# TiltMouseSurfaceMount.net
KiCad netlist of a schematic drawn in EAGLE
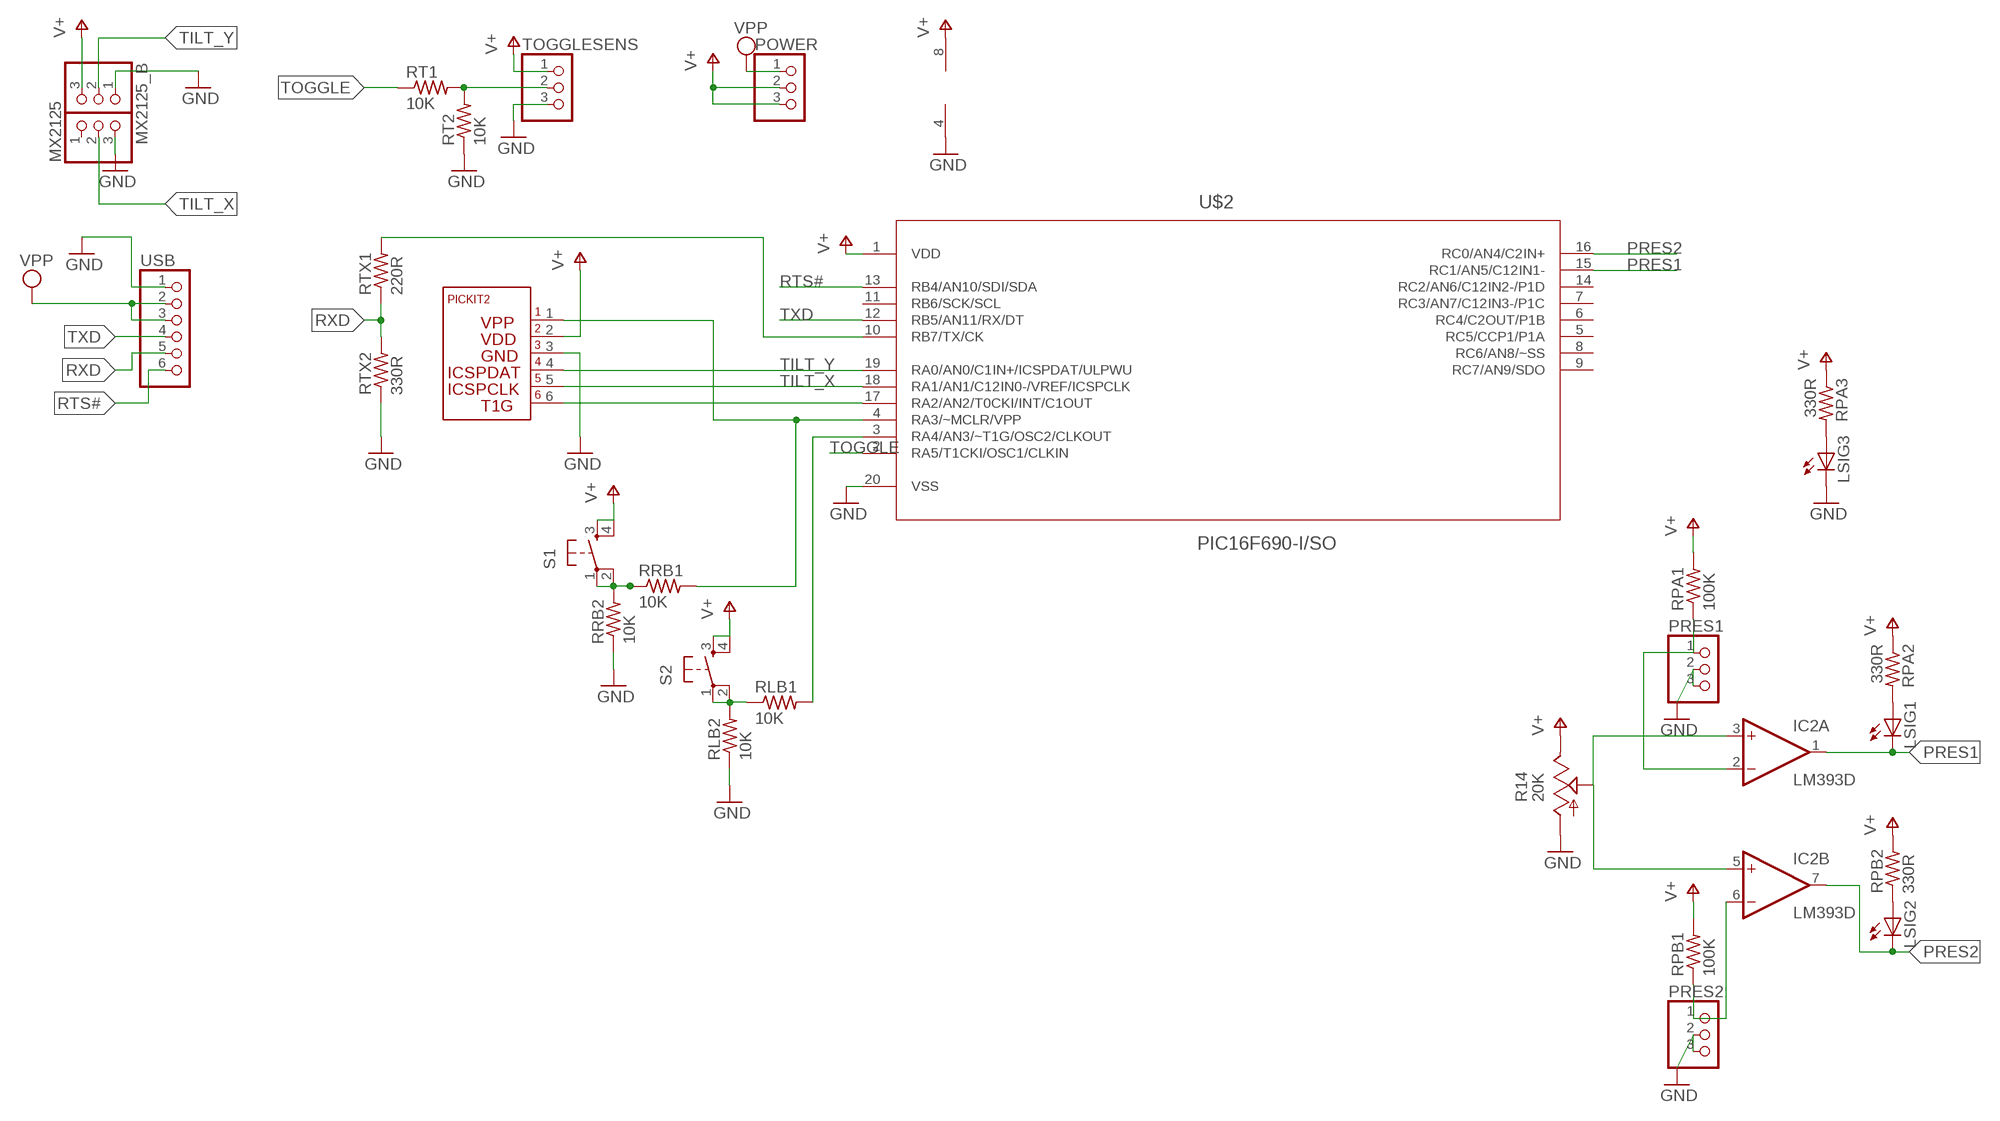
[diagram p0: schematic, sheet 1]

(export (version "E")
  (design (tool "Eeschema 10.0.6"))
  (components
    (comp (ref "IC2")
      (value "LM393D")
      (footprint "eagle-import:SO08")
      (libsource (lib "eagle-import") (part "LM393D"))
    )
    (comp (ref "LSIG1")
      (value "LEDSMT1206")
      (footprint "eagle-import:1206")
      (libsource (lib "eagle-import") (part "LEDSMT1206"))
    )
    (comp (ref "LSIG2")
      (value "LEDSMT1206")
      (footprint "eagle-import:1206")
      (libsource (lib "eagle-import") (part "LEDSMT1206"))
    )
    (comp (ref "LSIG3")
      (value "LEDSMT1206")
      (footprint "eagle-import:1206")
      (libsource (lib "eagle-import") (part "LEDSMT1206"))
    )
    (comp (ref "MX2125")
      (value "PINHD-1X3")
      (footprint "eagle-import:1X03")
      (libsource (lib "eagle-import") (part "PINHD-1X3"))
    )
    (comp (ref "MX2125_B")
      (value "PINHD-1X3")
      (footprint "eagle-import:1X03")
      (libsource (lib "eagle-import") (part "PINHD-1X3"))
    )
    (comp (ref "POWER")
      (value "PINHD-1X3")
      (footprint "eagle-import:1X03")
      (libsource (lib "eagle-import") (part "PINHD-1X3"))
    )
    (comp (ref "PRES1")
      (value "PINHD-1X3/90")
      (footprint "eagle-import:1X03_90")
      (libsource (lib "eagle-import") (part "PINHD-1X3/90"))
    )
    (comp (ref "PRES2")
      (value "PINHD-1X3/90")
      (footprint "eagle-import:1X03_90")
      (libsource (lib "eagle-import") (part "PINHD-1X3/90"))
    )
    (comp (ref "R14")
      (value "20K")
      (footprint "eagle-import:SM-42_43A")
      (libsource (lib "eagle-import") (part "TRIM_US-SM-42/43A"))
    )
    (comp (ref "RLB1")
      (value "10K")
      (footprint "eagle-import:R0805")
      (libsource (lib "eagle-import") (part "R-US_R0805"))
    )
    (comp (ref "RLB2")
      (value "10K")
      (footprint "eagle-import:R0805")
      (libsource (lib "eagle-import") (part "R-US_R0805"))
    )
    (comp (ref "RPA1")
      (value "100K")
      (footprint "eagle-import:R0805")
      (libsource (lib "eagle-import") (part "R-US_R0805"))
    )
    (comp (ref "RPA2")
      (value "330R")
      (footprint "eagle-import:R0805")
      (libsource (lib "eagle-import") (part "R-US_R0805"))
    )
    (comp (ref "RPA3")
      (value "330R")
      (footprint "eagle-import:R0805")
      (libsource (lib "eagle-import") (part "R-US_R0805"))
    )
    (comp (ref "RPB1")
      (value "100K")
      (footprint "eagle-import:R0805")
      (libsource (lib "eagle-import") (part "R-US_R0805"))
    )
    (comp (ref "RPB2")
      (value "330R")
      (footprint "eagle-import:R0805")
      (libsource (lib "eagle-import") (part "R-US_R0805"))
    )
    (comp (ref "RRB1")
      (value "10K")
      (footprint "eagle-import:R0805")
      (libsource (lib "eagle-import") (part "R-US_R0805"))
    )
    (comp (ref "RRB2")
      (value "10K")
      (footprint "eagle-import:R0805")
      (libsource (lib "eagle-import") (part "R-US_R0805"))
    )
    (comp (ref "RT1")
      (value "10K")
      (footprint "eagle-import:R0805")
      (libsource (lib "eagle-import") (part "R-US_R0805"))
    )
    (comp (ref "RT2")
      (value "10K")
      (footprint "eagle-import:R0805")
      (libsource (lib "eagle-import") (part "R-US_R0805"))
    )
    (comp (ref "RTX1")
      (value "220R")
      (footprint "eagle-import:R0805")
      (libsource (lib "eagle-import") (part "R-US_R0805"))
    )
    (comp (ref "RTX2")
      (value "330R")
      (footprint "eagle-import:R0805")
      (libsource (lib "eagle-import") (part "R-US_R0805"))
    )
    (comp (ref "S1")
      (value "TAC_SWITCHSMD")
      (footprint "eagle-import:TACTILE_SWITCH_SMD")
      (libsource (lib "eagle-import") (part "TAC_SWITCHSMD"))
    )
    (comp (ref "S2")
      (value "TAC_SWITCHSMD")
      (footprint "eagle-import:TACTILE_SWITCH_SMD")
      (libsource (lib "eagle-import") (part "TAC_SWITCHSMD"))
    )
    (comp (ref "TOGGLESENS")
      (value "PINHD-1X3")
      (footprint "eagle-import:1X03")
      (libsource (lib "eagle-import") (part "PINHD-1X3"))
    )
    (comp (ref "U$2")
      (value "PIC16F690-I/SO")
      (footprint "eagle-import:SOIC127P1030X265-20N")
      (libsource (lib "eagle-import") (part "PIC16F690-I/SO"))
    )
    (comp (ref "U$3")
      (value "PICKIT-ICSP")
      (footprint "eagle-import:PICKITJUMPER")
      (libsource (lib "eagle-import") (part "PICKIT-ICSP"))
    )
    (comp (ref "USB")
      (value "PINHD-1X6/90")
      (footprint "eagle-import:1X06_90")
      (libsource (lib "eagle-import") (part "PINHD-1X6/90"))
    )
  )
  (nets
    (net (code "1") (name "GND") (class "Default")
      (node (ref "IC2") (pin "4") (pinfunction "V-_4") (pintype "power_in"))
      (node (ref "LSIG3") (pin "C") (pinfunction "C_C") (pintype "passive"))
      (node (ref "MX2125") (pin "3") (pinfunction "3_3") (pintype "passive"))
      (node (ref "MX2125_B") (pin "1") (pinfunction "1_1") (pintype "passive"))
      (node (ref "PRES1") (pin "2") (pinfunction "2_2") (pintype "passive"))
      (node (ref "PRES1") (pin "3") (pinfunction "3_3") (pintype "passive"))
      (node (ref "PRES2") (pin "2") (pinfunction "2_2") (pintype "passive"))
      (node (ref "PRES2") (pin "3") (pinfunction "3_3") (pintype "passive"))
      (node (ref "R14") (pin "1") (pinfunction "A_1") (pintype "passive"))
      (node (ref "RLB2") (pin "1") (pinfunction "1_1") (pintype "passive"))
      (node (ref "RRB2") (pin "1") (pinfunction "1_1") (pintype "passive"))
      (node (ref "RT2") (pin "1") (pinfunction "1_1") (pintype "passive"))
      (node (ref "RTX2") (pin "1") (pinfunction "1_1") (pintype "passive"))
      (node (ref "TOGGLESENS") (pin "3") (pinfunction "3_3") (pintype "passive"))
      (node (ref "U$2") (pin "20") (pinfunction "VSS_20") (pintype "power_in"))
      (node (ref "U$3") (pin "3") (pinfunction "P$3_3") (pintype "bidirectional"))
      (node (ref "USB") (pin "1") (pinfunction "1_1") (pintype "passive"))
    )
    (net (code "2") (name "Net-(IC2A-+IN)") (class "Default")
      (node (ref "IC2") (pin "3") (pinfunction "+IN_3") (pintype "input"))
      (node (ref "IC2") (pin "5") (pinfunction "+IN_5") (pintype "input"))
      (node (ref "R14") (pin "2") (pinfunction "S_2") (pintype "passive"))
    )
    (net (code "3") (name "Net-(IC2A--IN)") (class "Default")
      (node (ref "IC2") (pin "2") (pinfunction "-IN_2") (pintype "input"))
      (node (ref "PRES1") (pin "1") (pinfunction "1_1") (pintype "passive"))
      (node (ref "RPA1") (pin "1") (pinfunction "1_1") (pintype "passive"))
    )
    (net (code "4") (name "Net-(IC2B--IN)") (class "Default")
      (node (ref "IC2") (pin "6") (pinfunction "-IN_6") (pintype "input"))
      (node (ref "PRES2") (pin "1") (pinfunction "1_1") (pintype "passive"))
      (node (ref "RPB1") (pin "1") (pinfunction "1_1") (pintype "passive"))
    )
    (net (code "5") (name "Net-(LSIG1-PadA)") (class "Default")
      (node (ref "LSIG1") (pin "A") (pinfunction "A_A") (pintype "passive"))
      (node (ref "RPA2") (pin "2") (pinfunction "2_2") (pintype "passive"))
    )
    (net (code "6") (name "Net-(LSIG2-PadA)") (class "Default")
      (node (ref "LSIG2") (pin "A") (pinfunction "A_A") (pintype "passive"))
      (node (ref "RPB2") (pin "1") (pinfunction "1_1") (pintype "passive"))
    )
    (net (code "7") (name "Net-(LSIG3-PadA)") (class "Default")
      (node (ref "LSIG3") (pin "A") (pinfunction "A_A") (pintype "passive"))
      (node (ref "RPA3") (pin "2") (pinfunction "2_2") (pintype "passive"))
    )
    (net (code "8") (name "Net-(RLB1-Pad1)") (class "Default")
      (node (ref "RLB1") (pin "1") (pinfunction "1_1") (pintype "passive"))
      (node (ref "RLB2") (pin "2") (pinfunction "2_2") (pintype "passive"))
      (node (ref "S2") (pin "1") (pinfunction "1_1") (pintype "passive"))
      (node (ref "S2") (pin "2") (pinfunction "2_2") (pintype "passive"))
    )
    (net (code "9") (name "Net-(RRB1-Pad1)") (class "Default")
      (node (ref "RRB1") (pin "1") (pinfunction "1_1") (pintype "passive"))
      (node (ref "RRB2") (pin "2") (pinfunction "2_2") (pintype "passive"))
      (node (ref "S1") (pin "1") (pinfunction "1_1") (pintype "passive"))
      (node (ref "S1") (pin "2") (pinfunction "2_2") (pintype "passive"))
    )
    (net (code "10") (name "Net-(RT1-Pad2)") (class "Default")
      (node (ref "RT1") (pin "2") (pinfunction "2_2") (pintype "passive"))
      (node (ref "RT2") (pin "2") (pinfunction "2_2") (pintype "passive"))
      (node (ref "TOGGLESENS") (pin "2") (pinfunction "2_2") (pintype "passive"))
    )
    (net (code "11") (name "Net-(U$2-RA2{slash}AN2{slash}T0CKI{slash}INT{slash}C1OUT)") (class "Default")
      (node (ref "U$2") (pin "17") (pinfunction "RA2/AN2/T0CKI/INT/C1OUT_17") (pintype "bidirectional"))
      (node (ref "U$3") (pin "6") (pinfunction "P$6_6") (pintype "bidirectional"))
    )
    (net (code "12") (name "Net-(U$2-RA3{slash}~{MCLR{slash}VPP})") (class "Default")
      (node (ref "RRB1") (pin "2") (pinfunction "2_2") (pintype "passive"))
      (node (ref "U$2") (pin "4") (pinfunction "RA3/~{MCLR/VPP}_4") (pintype "bidirectional"))
      (node (ref "U$3") (pin "1") (pinfunction "1_1") (pintype "bidirectional"))
    )
    (net (code "13") (name "Net-(U$2-RA4{slash}AN3{slash}~{T1G{slash}OSC2{slash}CLKOUT})") (class "Default")
      (node (ref "RLB1") (pin "2") (pinfunction "2_2") (pintype "passive"))
      (node (ref "U$2") (pin "3") (pinfunction "RA4/AN3/~{T1G/OSC2/CLKOUT}_3") (pintype "bidirectional"))
    )
    (net (code "14") (name "Net-(U$2-RB7{slash}TX{slash}CK)") (class "Default")
      (node (ref "RTX1") (pin "2") (pinfunction "2_2") (pintype "passive"))
      (node (ref "U$2") (pin "10") (pinfunction "RB7/TX/CK_10") (pintype "bidirectional"))
    )
    (net (code "15") (name "PRES1") (class "Default")
      (node (ref "IC2") (pin "1") (pinfunction "OUT_1") (pintype "output"))
      (node (ref "LSIG1") (pin "C") (pinfunction "C_C") (pintype "passive"))
      (node (ref "U$2") (pin "15") (pinfunction "RC1/AN5/C12IN1-_15") (pintype "bidirectional"))
    )
    (net (code "16") (name "PRES2") (class "Default")
      (node (ref "IC2") (pin "7") (pinfunction "OUT_7") (pintype "output"))
      (node (ref "LSIG2") (pin "C") (pinfunction "C_C") (pintype "passive"))
      (node (ref "U$2") (pin "16") (pinfunction "RC0/AN4/C2IN+_16") (pintype "bidirectional"))
    )
    (net (code "17") (name "RTS#") (class "Default")
      (node (ref "U$2") (pin "13") (pinfunction "RB4/AN10/SDI/SDA_13") (pintype "bidirectional"))
      (node (ref "USB") (pin "6") (pinfunction "6_6") (pintype "passive"))
    )
    (net (code "18") (name "RXD") (class "Default")
      (node (ref "RTX1") (pin "1") (pinfunction "1_1") (pintype "passive"))
      (node (ref "RTX2") (pin "2") (pinfunction "2_2") (pintype "passive"))
      (node (ref "USB") (pin "5") (pinfunction "5_5") (pintype "passive"))
    )
    (net (code "19") (name "TILT_X") (class "Default")
      (node (ref "MX2125") (pin "2") (pinfunction "2_2") (pintype "passive"))
      (node (ref "U$2") (pin "18") (pinfunction "RA1/AN1/C12IN0-/VREF/ICSPCLK_18") (pintype "bidirectional"))
      (node (ref "U$3") (pin "5") (pinfunction "P$5_5") (pintype "bidirectional"))
    )
    (net (code "20") (name "TILT_Y") (class "Default")
      (node (ref "MX2125_B") (pin "2") (pinfunction "2_2") (pintype "passive"))
      (node (ref "U$2") (pin "19") (pinfunction "RA0/AN0/C1IN+/ICSPDAT/ULPWU_19") (pintype "bidirectional"))
      (node (ref "U$3") (pin "4") (pinfunction "P$4_4") (pintype "bidirectional"))
    )
    (net (code "21") (name "TOGGLE") (class "Default")
      (node (ref "RT1") (pin "1") (pinfunction "1_1") (pintype "passive"))
      (node (ref "U$2") (pin "2") (pinfunction "RA5/T1CKI/OSC1/CLKIN_2") (pintype "bidirectional"))
    )
    (net (code "22") (name "TXD") (class "Default")
      (node (ref "U$2") (pin "12") (pinfunction "RB5/AN11/RX/DT_12") (pintype "bidirectional"))
      (node (ref "USB") (pin "4") (pinfunction "4_4") (pintype "passive"))
    )
    (net (code "23") (name "V+") (class "Default")
      (node (ref "IC2") (pin "8") (pinfunction "V+_8") (pintype "power_in"))
      (node (ref "MX2125_B") (pin "3") (pinfunction "3_3") (pintype "passive"))
      (node (ref "POWER") (pin "2") (pinfunction "2_2") (pintype "passive"))
      (node (ref "POWER") (pin "3") (pinfunction "3_3") (pintype "passive"))
      (node (ref "R14") (pin "3") (pinfunction "E_3") (pintype "passive"))
      (node (ref "RPA1") (pin "2") (pinfunction "2_2") (pintype "passive"))
      (node (ref "RPA2") (pin "1") (pinfunction "1_1") (pintype "passive"))
      (node (ref "RPA3") (pin "1") (pinfunction "1_1") (pintype "passive"))
      (node (ref "RPB1") (pin "2") (pinfunction "2_2") (pintype "passive"))
      (node (ref "RPB2") (pin "2") (pinfunction "2_2") (pintype "passive"))
      (node (ref "S1") (pin "3") (pinfunction "3_3") (pintype "passive"))
      (node (ref "S1") (pin "4") (pinfunction "4_4") (pintype "passive"))
      (node (ref "S2") (pin "3") (pinfunction "3_3") (pintype "passive"))
      (node (ref "S2") (pin "4") (pinfunction "4_4") (pintype "passive"))
      (node (ref "TOGGLESENS") (pin "1") (pinfunction "1_1") (pintype "passive"))
      (node (ref "U$2") (pin "1") (pinfunction "VDD_1") (pintype "power_in"))
      (node (ref "U$3") (pin "2") (pinfunction "P$2_2") (pintype "bidirectional"))
    )
    (net (code "24") (name "VPP") (class "Default")
      (node (ref "POWER") (pin "1") (pinfunction "1_1") (pintype "passive"))
      (node (ref "USB") (pin "2") (pinfunction "2_2") (pintype "passive"))
      (node (ref "USB") (pin "3") (pinfunction "3_3") (pintype "passive"))
    )
    (net (code "25") (name "unconnected-(MX2125-Pad1)") (class "Default")
      (node (ref "MX2125") (pin "1") (pinfunction "1_1") (pintype "passive"))
    )
    (net (code "26") (name "unconnected-(U$2-RB6{slash}SCK{slash}SCL-Pad11)") (class "Default")
      (node (ref "U$2") (pin "11") (pinfunction "RB6/SCK/SCL_11") (pintype "bidirectional"))
    )
    (net (code "27") (name "unconnected-(U$2-RC2{slash}AN6{slash}C12IN2-{slash}P1D-Pad14)") (class "Default")
      (node (ref "U$2") (pin "14") (pinfunction "RC2/AN6/C12IN2-/P1D_14") (pintype "bidirectional"))
    )
    (net (code "28") (name "unconnected-(U$2-RC3{slash}AN7{slash}C12IN3-{slash}P1C-Pad7)") (class "Default")
      (node (ref "U$2") (pin "7") (pinfunction "RC3/AN7/C12IN3-/P1C_7") (pintype "bidirectional"))
    )
    (net (code "29") (name "unconnected-(U$2-RC4{slash}C2OUT{slash}P1B-Pad6)") (class "Default")
      (node (ref "U$2") (pin "6") (pinfunction "RC4/C2OUT/P1B_6") (pintype "bidirectional"))
    )
    (net (code "30") (name "unconnected-(U$2-RC5{slash}CCP1{slash}P1A-Pad5)") (class "Default")
      (node (ref "U$2") (pin "5") (pinfunction "RC5/CCP1/P1A_5") (pintype "bidirectional"))
    )
    (net (code "31") (name "unconnected-(U$2-RC6{slash}AN8{slash}~{SS}-Pad8)") (class "Default")
      (node (ref "U$2") (pin "8") (pinfunction "RC6/AN8/~{SS}_8") (pintype "bidirectional"))
    )
    (net (code "32") (name "unconnected-(U$2-RC7{slash}AN9{slash}SDO-Pad9)") (class "Default")
      (node (ref "U$2") (pin "9") (pinfunction "RC7/AN9/SDO_9") (pintype "bidirectional"))
    )
  )
)
